# FRONT-UNIT-7.net
KiCad netlist of a schematic drawn in Altium Designer
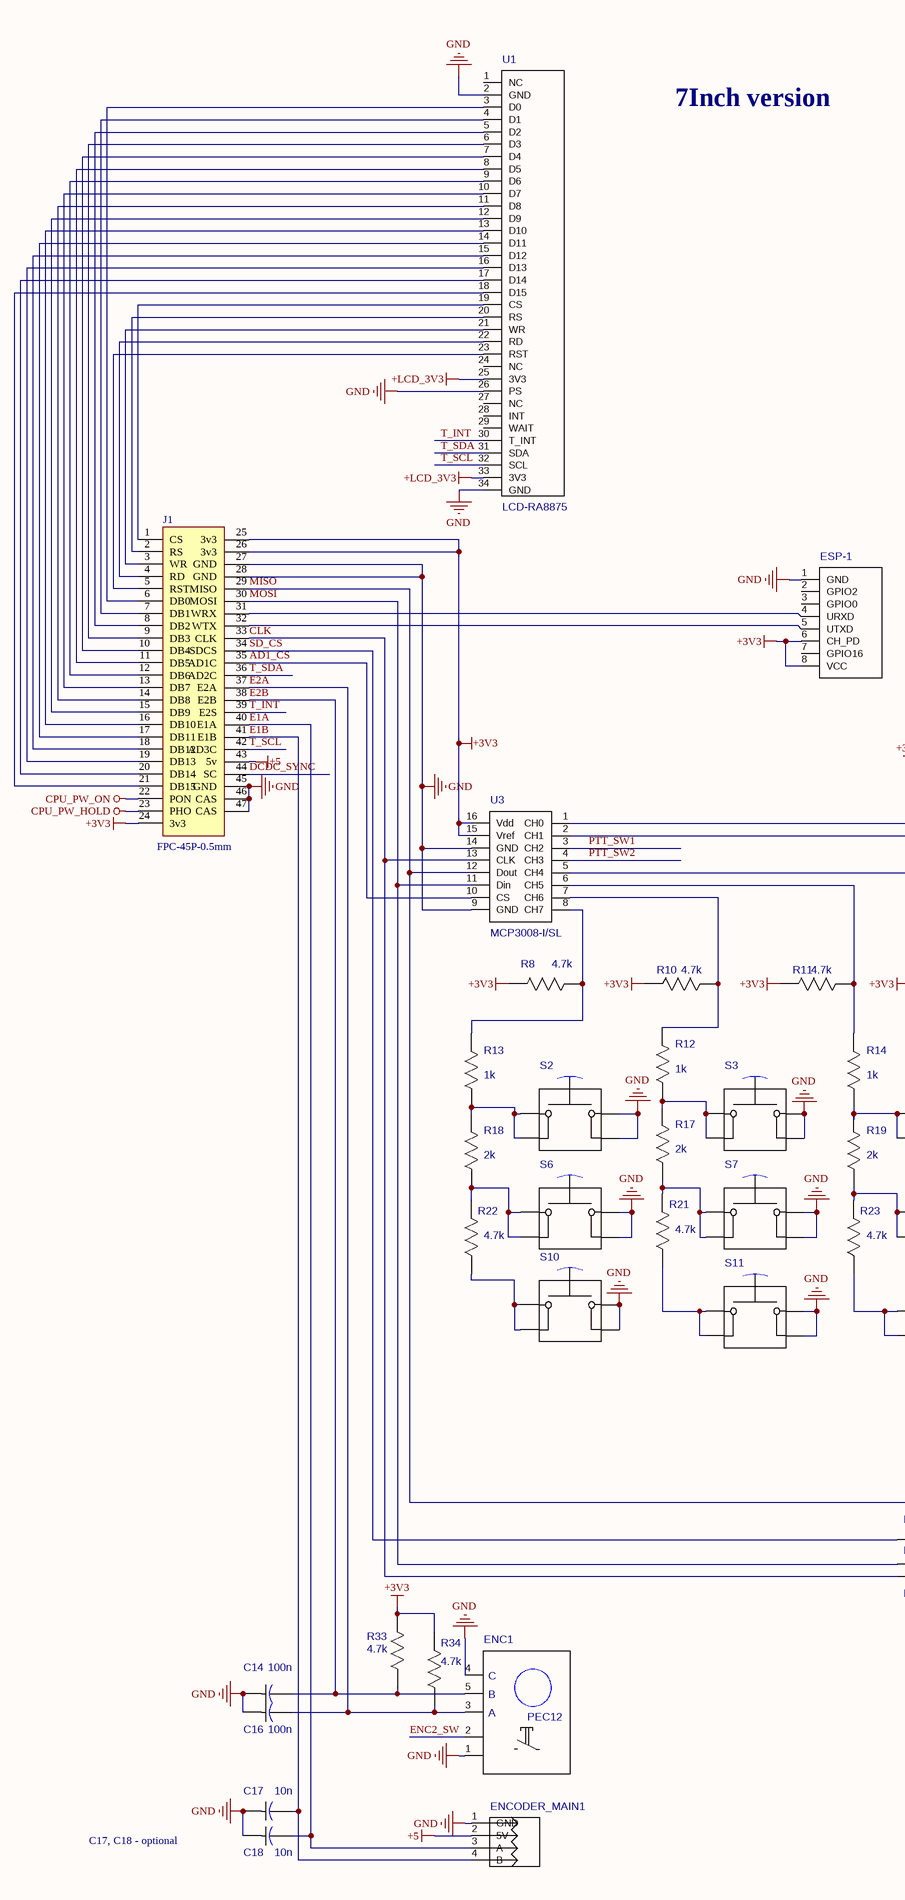
[diagram p0: FRONT-UNIT-7.SCHDOC, left]
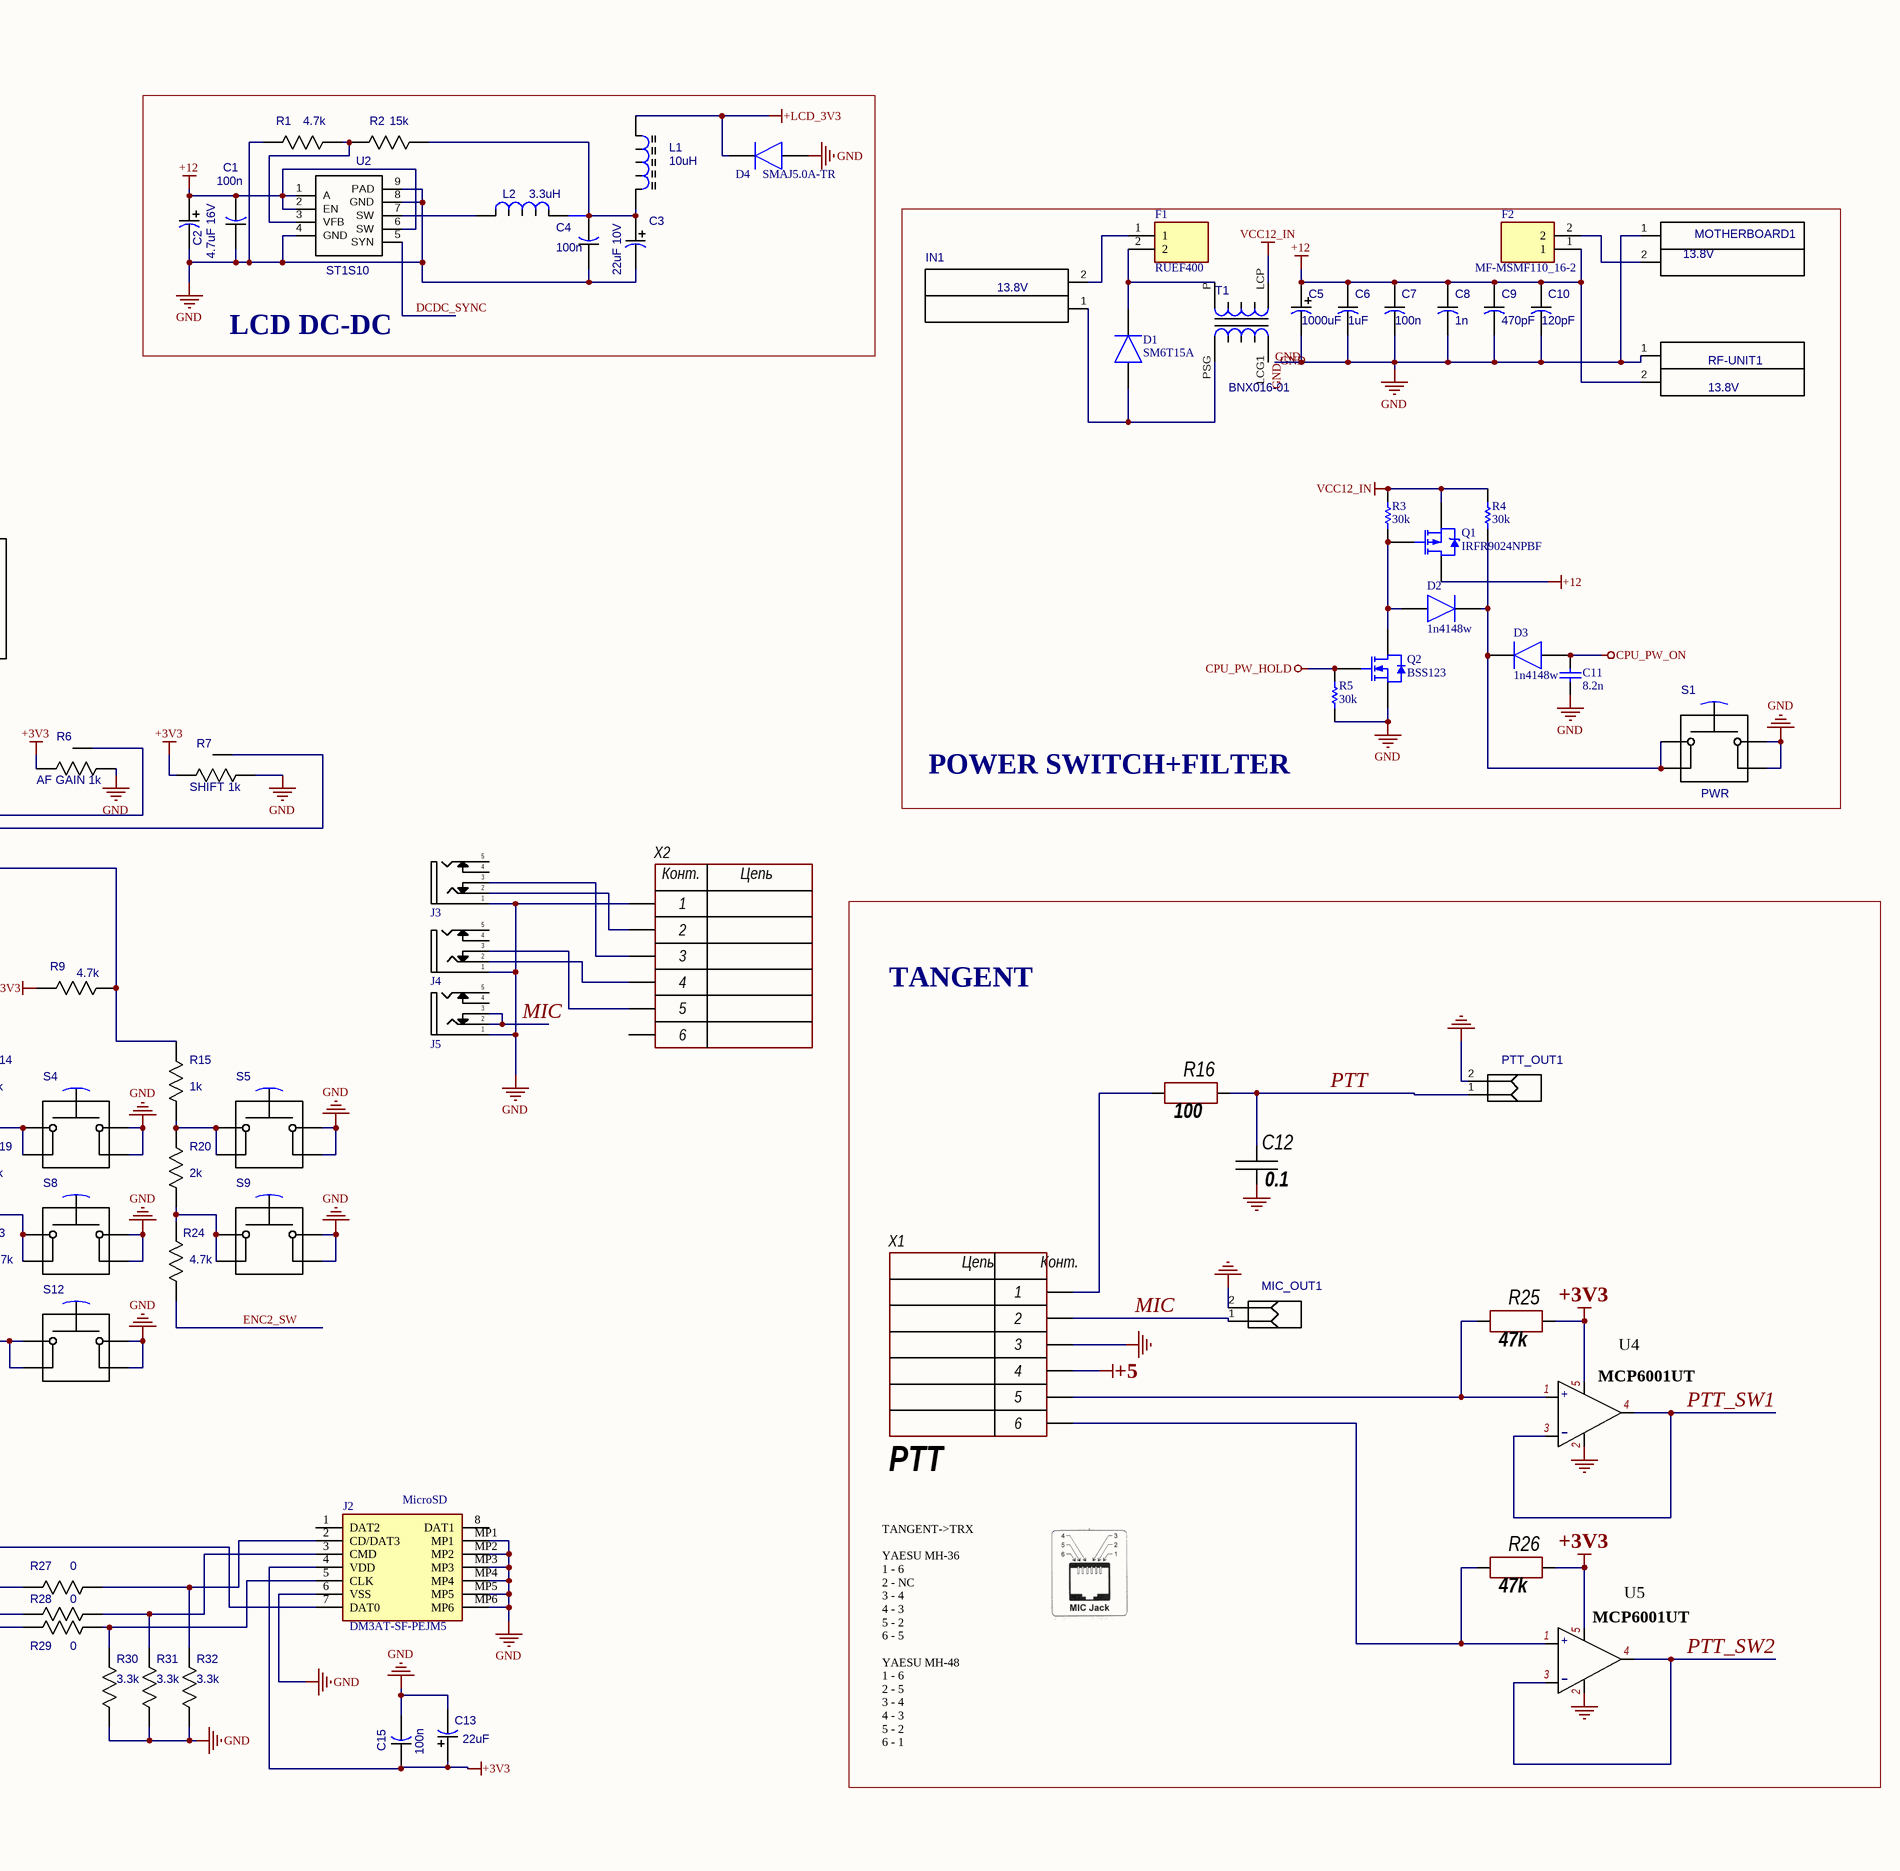
[diagram p1: FRONT-UNIT-7.SCHDOC, right]

(export (version "E")
  (design (tool "Eeschema 10.0.6"))
  (components
    (comp (ref "C1")
      (value "100n")
      (footprint "CAP_0805")
      (description "CAP_0805")
      (libsource (lib "*") (part "CAP_0805"))
    )
    (comp (ref "C2")
      (value "4.7uF 16V")
      (footprint "CAPAE_6.6x6.6h5.4")
      (description "CAPAE_6.6x6.6h5.4")
      (libsource (lib "*") (part "CAPAE_6.6x6.6h5.4"))
    )
    (comp (ref "C3")
      (value "22uF 10V")
      (footprint "CAPAE_4.3x4.3h5.4")
      (description "CAPAE_4.3x4.3h5.4")
      (libsource (lib "*") (part "CAPAE_4.3x4.3h5.4"))
    )
    (comp (ref "C4")
      (value "100n")
      (footprint "CAP_0805")
      (description "CAP_0805")
      (libsource (lib "FRONT-UNIT-7INCH") (part "CAP_0805"))
    )
    (comp (ref "C5")
      (value "1000uF")
      (footprint "CAP250RP")
      (description "CAP250RP")
      (libsource (lib "*") (part "CAP250RP"))
    )
    (comp (ref "C6")
      (value "1uF")
      (footprint "CAP_1206")
      (description "CAP_1206")
      (libsource (lib "*") (part "CAP_1206"))
    )
    (comp (ref "C7")
      (value "100n")
      (footprint "CAP_1206")
      (description "CAP_1206")
      (libsource (lib "*") (part "CAP_1206"))
    )
    (comp (ref "C8")
      (value "1n")
      (footprint "CAP_1206")
      (description "CAP_1206")
      (libsource (lib "*") (part "CAP_1206"))
    )
    (comp (ref "C9")
      (value "470pF")
      (footprint "CAP_1206")
      (description "CAP_1206")
      (libsource (lib "*") (part "CAP_1206"))
    )
    (comp (ref "C10")
      (value "120pF")
      (footprint "CAP_1206")
      (description "CAP_1206")
      (libsource (lib "FRONT-UNIT-7INCH") (part "CAP_1206"))
    )
    (comp (ref "C11")
      (value "8.2n")
      (footprint "CAPC2013X94X50LL20T25")
      (description "CAP_1206")
      (fields
        (field (name "MANUFACTURER") "AVX Interconnect / Elco")
        (field (name "PART NUMBER") "08055C822KAT2A")
      )
      (libsource (lib "Altium Content Vault") (part "CAP"))
    )
    (comp (ref "C12")
      (value "0.1")
      (footprint "CH0805C")
      (libsource (lib "FRONT-UNIT-7INCH") (part "Capacitor"))
    )
    (comp (ref "C13")
      (value "22uF")
      (footprint "EEEFC_sizeB")
      (description "EEEFC_sizeB")
      (libsource (lib "*") (part "EEEFC_sizeB"))
    )
    (comp (ref "C14")
      (value "100n")
      (footprint "CAP_0805")
      (description "CAP_0805")
      (libsource (lib "*") (part "CAP_0805"))
    )
    (comp (ref "C15")
      (value "100n")
      (footprint "CAP_0805")
      (description "CAP_0805")
      (libsource (lib "*") (part "CAP_0805"))
    )
    (comp (ref "C16")
      (value "100n")
      (footprint "CAP_0805")
      (description "CAP_0805")
      (libsource (lib "*") (part "CAP_0805"))
    )
    (comp (ref "C17")
      (value "10n")
      (footprint "CAP_0805")
      (description "CAP_0805")
      (libsource (lib "*") (part "CAP_0805"))
    )
    (comp (ref "C18")
      (value "10n")
      (footprint "CAP_0805")
      (description "CAP_0805")
      (libsource (lib "*") (part "CAP_0805"))
    )
    (comp (ref "D1")
      (value "SM6T15A")
      (footprint "SamacSys:SMBJ36CATR")
      (description "Diode")
      (fields (field (name "MOUSER PART NUMBER") "511-SM6T15A") (field (name "RS PART NUMBER") "4864915P"))
      (libsource (lib "*") (part "SM6T15A"))
    )
    (comp (ref "D2")
      (value "1n4148w")
      (footprint "SamacSys:SOD3716X135N")
      (description "Diode")
      (libsource (lib "*") (part "1n4148w"))
    )
    (comp (ref "D3")
      (value "1n4148w")
      (footprint "SamacSys:SOD3716X135N")
      (description "Diode")
      (libsource (lib "*") (part "1n4148w"))
    )
    (comp (ref "D4")
      (value "SMAJ5.0A-TR")
      (footprint "SamacSys:SMBJ36CATR")
      (description "Diode")
      (fields
        (field (name "MANUFACTURER_PART_NUMBER") "SMLVT3V3")
        (field (name "MOUSER PART NUMBER") "511-SMLVT3V3")
      )
      (libsource (lib "*") (part "SMLVT3V3"))
    )
    (comp (ref "ENC1") (value "PEC12") (footprint "PEC12") (libsource (lib "*") (part "PEC12")))
    (comp (ref "ENCODER_MAIN1")
      (value "OPTICAL ENCODER")
      (footprint "644456-4")
      (libsource (lib "*") (part "644456-4"))
    )
    (comp (ref "ESP-1")
      (value "ESP-01 ESP8266")
      (footprint "ESP-01 ESP8266")
      (libsource (lib "*") (part "ESP-01 ESP8266"))
    )
    (comp (ref "F1")
      (value "RUEF400")
      (footprint "SamacSys:RUEF400")
      (description "Fuse")
      (fields (field (name "MOUSER PART NUMBER") "650-RUEF400") (field (name "RS PART NUMBER") "5176837P"))
      (libsource (lib "*") (part "RUEF400"))
    )
    (comp (ref "F2")
      (value "MF-MSMF110_16-2")
      (footprint "SamacSys:FUSC4632X85N")
      (description "Fuse")
      (fields
        (field (name "MANUFACTURER_PART_NUMBER") "MF-MSMF110/16-2")
        (field (name "MOUSER PART NUMBER") "652-MF-MSMF110/16-2")
      )
      (libsource (lib "*") (part "MF-MSMF110_16-2"))
    )
    (comp (ref "IN1")
      (value "13.8V")
      (footprint "JX2")
      (description "JX2")
      (libsource (lib "*") (part "JX2"))
    )
    (comp (ref "J1")
      (value "FPC-45P-0.5mm")
      (footprint "FH12S45S05SH60")
      (description "Connector")
      (fields
        (field (name "MANUFACTURER_PART_NUMBER") "FH12S-45S-0.5SH(55)")
        (field (name "MOUSER PART NUMBER") "798-FH12S-45S-05SH55")
      )
      (libsource (lib "*") (part "FH12S-45S-0.5SH_55_"))
    )
    (comp (ref "J2")
      (value "DM3AT-SF-PEJM5")
      (footprint "SamacSys:DM3ATSFPEJM5")
      (description "Connector")
      (libsource (lib "*") (part "DM3AT-SF-PEJM5"))
    )
    (comp (ref "J3") (value "PJ-3,5") (footprint "Audio-PJ-392") (libsource (lib "SDR_ham") (part "PJ-3,5")))
    (comp (ref "J4") (value "PJ-3,5") (footprint "Audio-PJ-392") (libsource (lib "SDR_ham") (part "PJ-3,5")))
    (comp (ref "J5") (value "PJ-3,5") (footprint "Audio-PJ-392") (libsource (lib "SDR_ham") (part "PJ-3,5")))
    (comp (ref "L1")
      (value "10uH")
      (footprint "IND_FERRITE_CORE")
      (description "Inductor")
      (libsource (lib "FRONT-UNIT-7INCH") (part "IND_FERRITE_CORE"))
    )
    (comp (ref "L2")
      (value "3.3uH")
      (footprint "IND_1812")
      (description "IND_1812")
      (libsource (lib "*") (part "IND_1812"))
    )
    (comp (ref "MIC_OUT1")
      (value "MIC_OUT")
      (footprint "51022-0200")
      (description "51022-0200")
      (libsource (lib "*") (part "51022-0200"))
    )
    (comp (ref "MOTHERBOARD1")
      (value "13.8V")
      (footprint "JX2")
      (description "JX2")
      (libsource (lib "*") (part "JX2"))
    )
    (comp (ref "PTT_OUT1")
      (value "PTT_OUT")
      (footprint "51022-0200")
      (description "51022-0200")
      (libsource (lib "*") (part "51022-0200"))
    )
    (comp (ref "Q1")
      (value "IRFR9024NPBF")
      (footprint "ONSC-DPAK-3-369C-01_V")
      (description "IRFR9024NPBF, Транзистор, Р-канал 55В 11А")
      (fields (field (name "MANUFACTURER") "On Semiconductor") (field (name "PARTNUMBER") "NTD2955G"))
      (libsource (lib "Altium Content Vault") (part "ONSC-PMOS-G1S3D4-3_B"))
    )
    (comp (ref "Q2")
      (value "BSS123")
      (footprint "FAIR-SOT23-3_V")
      (fields (field (name "MANUFACTURER") "Fairchild"))
      (libsource (lib "Altium Content Vault") (part "NEMOS-GSD-3"))
    )
    (comp (ref "R1")
      (value "4.7k")
      (footprint "RES_0805")
      (description "RES_0805")
      (libsource (lib "") (part "RES_0805_1"))
    )
    (comp (ref "R2")
      (value "15k")
      (footprint "RES_0805")
      (description "RES_0805")
      (fields (field (name "Comment") "120k+100k"))
      (libsource (lib "") (part "RES_0805_1"))
    )
    (comp (ref "R3")
      (value "30k")
      (footprint "RESC2013X60X40NL20T25")
      (description "RES_0805")
      (fields (field (name "MANUFACTURER") "Panasonic") (field (name "PART NUMBER") "ERA-6AEB303V"))
      (libsource (lib "Altium Content Vault") (part "RES"))
    )
    (comp (ref "R4")
      (value "30k")
      (footprint "RESC2013X60X40NL20T25")
      (description "RES_0805")
      (fields (field (name "MANUFACTURER") "Panasonic") (field (name "PART NUMBER") "ERA-6AEB303V"))
      (libsource (lib "Altium Content Vault") (part "RES"))
    )
    (comp (ref "R5")
      (value "30k")
      (footprint "RESC2013X60X40NL20T25")
      (description "RES_0805")
      (fields (field (name "MANUFACTURER") "Panasonic") (field (name "PART NUMBER") "ERA-6AEB303V"))
      (libsource (lib "Altium Content Vault") (part "RES"))
    )
    (comp (ref "R6")
      (value "AF GAIN 1k")
      (footprint "PTV09")
      (description "Adjustable Resistor PTV09")
      (fields (field (name "Comment") "ptv09a-4225f-b102"))
      (libsource (lib "*") (part "PTV09"))
    )
    (comp (ref "R7")
      (value "SHIFT 1k")
      (footprint "PTV09")
      (description "Adjustable Resistor PTV09")
      (fields (field (name "Comment") "ptv09a-4225f-b102"))
      (libsource (lib "*") (part "PTV09"))
    )
    (comp (ref "R8")
      (value "4.7k")
      (footprint "RES_0805")
      (description "RES_0805")
      (libsource (lib "*") (part "RES_0805"))
    )
    (comp (ref "R9")
      (value "4.7k")
      (footprint "RES_0805")
      (description "RES_0805")
      (libsource (lib "*") (part "RES_0805"))
    )
    (comp (ref "R10")
      (value "4.7k")
      (footprint "RES_0805")
      (description "RES_0805")
      (libsource (lib "*") (part "RES_0805"))
    )
    (comp (ref "R11")
      (value "4.7k")
      (footprint "RES_0805")
      (description "RES_0805")
      (libsource (lib "*") (part "RES_0805"))
    )
    (comp (ref "R12")
      (value "1k")
      (footprint "RES_0805")
      (description "RES_0805")
      (libsource (lib "*") (part "RES_0805"))
    )
    (comp (ref "R13")
      (value "1k")
      (footprint "RES_0805")
      (description "RES_0805")
      (libsource (lib "*") (part "RES_0805"))
    )
    (comp (ref "R14")
      (value "1k")
      (footprint "RES_0805")
      (description "RES_0805")
      (libsource (lib "*") (part "RES_0805"))
    )
    (comp (ref "R15")
      (value "1k")
      (footprint "RES_0805")
      (description "RES_0805")
      (libsource (lib "*") (part "RES_0805"))
    )
    (comp (ref "R16")
      (value "100")
      (footprint "FRONT-UNIT-7INCH:CH0805R")
      (libsource (lib "Discrete") (part "Resistor"))
    )
    (comp (ref "R17")
      (value "2k")
      (footprint "RES_0805")
      (description "RES_0805")
      (libsource (lib "*") (part "RES_0805"))
    )
    (comp (ref "R18")
      (value "2k")
      (footprint "RES_0805")
      (description "RES_0805")
      (libsource (lib "*") (part "RES_0805"))
    )
    (comp (ref "R19")
      (value "2k")
      (footprint "RES_0805")
      (description "RES_0805")
      (libsource (lib "*") (part "RES_0805"))
    )
    (comp (ref "R20")
      (value "2k")
      (footprint "RES_0805")
      (description "RES_0805")
      (libsource (lib "*") (part "RES_0805"))
    )
    (comp (ref "R21")
      (value "4.7k")
      (footprint "RES_0805")
      (description "RES_0805")
      (libsource (lib "*") (part "RES_0805"))
    )
    (comp (ref "R22")
      (value "4.7k")
      (footprint "RES_0805")
      (description "RES_0805")
      (libsource (lib "*") (part "RES_0805"))
    )
    (comp (ref "R23")
      (value "4.7k")
      (footprint "RES_0805")
      (description "RES_0805")
      (libsource (lib "*") (part "RES_0805"))
    )
    (comp (ref "R24")
      (value "4.7k")
      (footprint "RES_0805")
      (description "RES_0805")
      (libsource (lib "*") (part "RES_0805"))
    )
    (comp (ref "R25")
      (value "47k")
      (footprint "FRONT-UNIT-7INCH:CH0805R")
      (libsource (lib "Discrete") (part "Resistor"))
    )
    (comp (ref "R26")
      (value "47k")
      (footprint "FRONT-UNIT-7INCH:CH0805C")
      (libsource (lib "Discrete") (part "Resistor"))
    )
    (comp (ref "R27")
      (value "0")
      (footprint "RES_0805")
      (description "RES_0805")
      (libsource (lib "*") (part "RES_0805"))
    )
    (comp (ref "R28")
      (value "0")
      (footprint "RES_0805")
      (description "RES_0805")
      (libsource (lib "*") (part "RES_0805"))
    )
    (comp (ref "R29")
      (value "0")
      (footprint "RES_0805")
      (description "RES_0805")
      (libsource (lib "*") (part "RES_0805"))
    )
    (comp (ref "R30")
      (value "3.3k")
      (footprint "RES_0805")
      (description "RES_0805")
      (libsource (lib "*") (part "RES_0805"))
    )
    (comp (ref "R31")
      (value "3.3k")
      (footprint "RES_0805")
      (description "RES_0805")
      (libsource (lib "*") (part "RES_0805"))
    )
    (comp (ref "R32")
      (value "3.3k")
      (footprint "RES_0805")
      (description "RES_0805")
      (libsource (lib "*") (part "RES_0805"))
    )
    (comp (ref "R33")
      (value "4.7k")
      (footprint "RES_0805")
      (description "RES_0805")
      (libsource (lib "*") (part "RES_0805"))
    )
    (comp (ref "R34")
      (value "4.7k")
      (footprint "RES_0805")
      (description "RES_0805")
      (libsource (lib "*") (part "RES_0805"))
    )
    (comp (ref "RF-UNIT1")
      (value "13.8V")
      (footprint "JX2")
      (description "JX2")
      (libsource (lib "*") (part "JX2"))
    )
    (comp (ref "S1")
      (value "PWR")
      (footprint "PTS645SK50LFS")
      (description "PTS645SK50LFS")
      (libsource (lib "*") (part "PTS645SK50LFS"))
    )
    (comp (ref "S2")
      (value "PTS645SK50LFS")
      (footprint "PTS645SK50LFS")
      (fields (field (name "LCSC PART #") "test"))
      (libsource (lib "*") (part "PTS645SK50LFS"))
    )
    (comp (ref "S3")
      (value "PTS645SK50LFS")
      (footprint "PTS645SK50LFS")
      (libsource (lib "*") (part "PTS645SK50LFS"))
    )
    (comp (ref "S4")
      (value "PTS645SK50LFS")
      (footprint "PTS645SK50LFS")
      (libsource (lib "*") (part "PTS645SK50LFS"))
    )
    (comp (ref "S5")
      (value "PTS645SK50LFS")
      (footprint "PTS645SK50LFS")
      (libsource (lib "*") (part "PTS645SK50LFS"))
    )
    (comp (ref "S6")
      (value "PTS645SK50LFS")
      (footprint "PTS645SK50LFS")
      (libsource (lib "*") (part "PTS645SK50LFS"))
    )
    (comp (ref "S7")
      (value "PTS645SK50LFS")
      (footprint "PTS645SK50LFS")
      (libsource (lib "*") (part "PTS645SK50LFS"))
    )
    (comp (ref "S8")
      (value "PTS645SK50LFS")
      (footprint "PTS645SK50LFS")
      (libsource (lib "*") (part "PTS645SK50LFS"))
    )
    (comp (ref "S9")
      (value "PTS645SK50LFS")
      (footprint "PTS645SK50LFS")
      (libsource (lib "*") (part "PTS645SK50LFS"))
    )
    (comp (ref "S10")
      (value "PTS645SK50LFS")
      (footprint "PTS645SK50LFS")
      (libsource (lib "*") (part "PTS645SK50LFS"))
    )
    (comp (ref "S11")
      (value "PTS645SK50LFS")
      (footprint "PTS645SK50LFS")
      (libsource (lib "*") (part "PTS645SK50LFS"))
    )
    (comp (ref "S12")
      (value "PTS645SK50LFS")
      (footprint "PTS645SK50LFS")
      (libsource (lib "*") (part "PTS645SK50LFS"))
    )
    (comp (ref "T1")
      (value "BNX016-01")
      (footprint "TRANSF_ICORE")
      (libsource (lib "*") (part "TRANSF_ICORE"))
    )
    (comp (ref "U1")
      (value "LCD-RA8875")
      (footprint "LCD-RA8875")
      (libsource (lib "FRONT-UNIT-7INCH") (part "LCD-RA8875"))
    )
    (comp (ref "U2") (value "ST1S10") (footprint "ST1S10") (libsource (lib "*") (part "ST1S10")))
    (comp (ref "U3")
      (value "MCP3008-I/SL")
      (footprint "MCP3008-I/SL")
      (libsource (lib "*") (part "MCP3008-I/SL"))
    )
    (comp (ref "U4")
      (value "MCP6001UT")
      (footprint "SOT23-5")
      (libsource (lib "Analog") (part "MCP6001UT_1"))
    )
    (comp (ref "U5")
      (value "MCP6001UT")
      (footprint "SOT23-5")
      (libsource (lib "Analog") (part "MCP6001UT_1"))
    )
    (comp (ref "X1")
      (value "PTT")
      (footprint "custom:CON: PLS-6")
      (libsource (lib "") (part "6-Connector_1"))
    )
    (comp (ref "X2")
      (value "PTT")
      (footprint "custom:CON: PLS-6")
      (libsource (lib "Connectors") (part "6-Connector"))
    )
  )
  (nets
    (net (code "1") (name "+3V3") (class "Default")
      (node (ref "C13") (pin "1") (pinfunction "PLUS_1") (pintype "passive"))
      (node (ref "C15") (pin "1") (pinfunction "1_1") (pintype "passive"))
      (node (ref "ESP-1") (pin "6") (pinfunction "CH_PD_6") (pintype "passive"))
      (node (ref "ESP-1") (pin "8") (pinfunction "VCC_8") (pintype "passive"))
      (node (ref "J1") (pin "24") (pinfunction "3v3_24") (pintype "passive"))
      (node (ref "J1") (pin "25") (pinfunction "3v3_25") (pintype "passive"))
      (node (ref "J1") (pin "26") (pinfunction "3v3_26") (pintype "passive"))
      (node (ref "J2") (pin "4") (pinfunction "VDD_4") (pintype "passive"))
      (node (ref "R10") (pin "2") (pinfunction "2_2") (pintype "passive"))
      (node (ref "R11") (pin "2") (pinfunction "2_2") (pintype "passive"))
      (node (ref "R25") (pin "2") (pinfunction "2_2") (pintype "passive"))
      (node (ref "R26") (pin "2") (pinfunction "2_2") (pintype "passive"))
      (node (ref "R33") (pin "2") (pinfunction "2_2") (pintype "passive"))
      (node (ref "R34") (pin "2") (pinfunction "2_2") (pintype "passive"))
      (node (ref "R6") (pin "1") (pinfunction "CW_1") (pintype "passive"))
      (node (ref "R7") (pin "1") (pinfunction "CW_1") (pintype "passive"))
      (node (ref "R8") (pin "2") (pinfunction "2_2") (pintype "passive"))
      (node (ref "R9") (pin "2") (pinfunction "2_2") (pintype "passive"))
      (node (ref "U3") (pin "15") (pinfunction "Vref_15") (pintype "passive"))
      (node (ref "U3") (pin "16") (pinfunction "Vdd_16") (pintype "passive"))
      (node (ref "U4") (pin "5") (pinfunction "5_5") (pintype "passive"))
      (node (ref "U5") (pin "5") (pinfunction "5_5") (pintype "passive"))
    )
    (net (code "2") (name "+5") (class "Default")
      (node (ref "ENCODER_MAIN1") (pin "2") (pinfunction "5V_2") (pintype "passive"))
      (node (ref "J1") (pin "43") (pinfunction "5v_43") (pintype "passive"))
      (node (ref "X1") (pin "4") (pinfunction "4_4") (pintype "power_in"))
    )
    (net (code "3") (name "+12") (class "Default")
      (node (ref "C1") (pin "2") (pinfunction "2_2") (pintype "passive"))
      (node (ref "C10") (pin "1") (pinfunction "1_1") (pintype "passive"))
      (node (ref "C2") (pin "1") (pinfunction "PLUS_1") (pintype "passive"))
      (node (ref "C5") (pin "1") (pinfunction "PLUS_1") (pintype "passive"))
      (node (ref "C6") (pin "1") (pinfunction "1_1") (pintype "passive"))
      (node (ref "C7") (pin "1") (pinfunction "1_1") (pintype "passive"))
      (node (ref "C8") (pin "1") (pinfunction "1_1") (pintype "passive"))
      (node (ref "C9") (pin "1") (pinfunction "1_1") (pintype "passive"))
      (node (ref "F2") (pin "1") (pinfunction "1_1") (pintype "passive"))
      (node (ref "Q1") (pin "4") (pinfunction "D_4") (pintype "passive"))
      (node (ref "RF-UNIT1") (pin "2") (pinfunction "1_2") (pintype "passive"))
      (node (ref "U2") (pin "1") (pinfunction "A_1") (pintype "passive"))
      (node (ref "U2") (pin "2") (pinfunction "EN_2") (pintype "passive"))
      (node (ref "U2") (pin "6") (pinfunction "SW_6") (pintype "passive"))
    )
    (net (code "4") (name "+LCD_3V3") (class "Default")
      (node (ref "D4") (pin "1") (pinfunction "K_1") (pintype "passive"))
      (node (ref "L1") (pin "1") (pinfunction "A_1") (pintype "passive"))
      (node (ref "U1") (pin "25") (pinfunction "3V3_25") (pintype "passive"))
      (node (ref "U1") (pin "33") (pinfunction "3V3_33") (pintype "passive"))
    )
    (net (code "5") (name "/AD1_CS") (class "Default")
      (node (ref "J1") (pin "35") (pinfunction "AD1C_35") (pintype "passive"))
      (node (ref "U3") (pin "10") (pinfunction "CS_10") (pintype "passive"))
    )
    (net (code "6") (name "/CLK") (class "Default")
      (node (ref "J1") (pin "33") (pinfunction "CLK_33") (pintype "passive"))
      (node (ref "R29") (pin "2") (pinfunction "2_2") (pintype "passive"))
      (node (ref "U3") (pin "13") (pinfunction "CLK_13") (pintype "passive"))
    )
    (net (code "7") (name "/DCDC_SYNC") (class "Default")
      (node (ref "J1") (pin "44") (pinfunction "SC_44") (pintype "passive"))
      (node (ref "U2") (pin "5") (pinfunction "SYN_5") (pintype "passive"))
    )
    (net (code "8") (name "/E1A") (class "Default")
      (node (ref "C18") (pin "2") (pinfunction "2_2") (pintype "passive"))
      (node (ref "ENCODER_MAIN1") (pin "3") (pinfunction "A_3") (pintype "passive"))
      (node (ref "J1") (pin "40") (pinfunction "E1A_40") (pintype "passive"))
    )
    (net (code "9") (name "/E1B") (class "Default")
      (node (ref "C17") (pin "2") (pinfunction "2_2") (pintype "passive"))
      (node (ref "ENCODER_MAIN1") (pin "4") (pinfunction "B_4") (pintype "passive"))
      (node (ref "J1") (pin "41") (pinfunction "E1B_41") (pintype "passive"))
    )
    (net (code "10") (name "/E2A") (class "Default")
      (node (ref "C16") (pin "2") (pinfunction "2_2") (pintype "passive"))
      (node (ref "ENC1") (pin "3") (pinfunction "A_3") (pintype "passive"))
      (node (ref "J1") (pin "37") (pinfunction "E2A_37") (pintype "passive"))
      (node (ref "R34") (pin "1") (pinfunction "1_1") (pintype "passive"))
    )
    (net (code "11") (name "/E2B") (class "Default")
      (node (ref "C14") (pin "2") (pinfunction "2_2") (pintype "passive"))
      (node (ref "ENC1") (pin "5") (pinfunction "B_5") (pintype "passive"))
      (node (ref "J1") (pin "38") (pinfunction "E2B_38") (pintype "passive"))
      (node (ref "R33") (pin "1") (pinfunction "1_1") (pintype "passive"))
    )
    (net (code "12") (name "/ENC2_SW") (class "Default")
      (node (ref "ENC1") (pin "2") (pinfunction "2_2") (pintype "passive"))
      (node (ref "R24") (pin "1") (pinfunction "1_1") (pintype "passive"))
    )
    (net (code "13") (name "/MIC") (class "Default")
      (node (ref "J5") (pin "2") (pinfunction "7_2") (pintype "passive"))
      (node (ref "J5") (pin "3") (pinfunction "6_3") (pintype "passive"))
      (node (ref "MIC_OUT1") (pin "1") (pinfunction "1_1") (pintype "passive"))
      (node (ref "X1") (pin "2") (pinfunction "2_2") (pintype "passive"))
    )
    (net (code "14") (name "/MISO") (class "Default")
      (node (ref "J1") (pin "29") (pinfunction "MISO_29") (pintype "passive"))
      (node (ref "J2") (pin "7") (pinfunction "DAT0_7") (pintype "passive"))
      (node (ref "U3") (pin "12") (pinfunction "Dout_12") (pintype "passive"))
    )
    (net (code "15") (name "/MOSI") (class "Default")
      (node (ref "J1") (pin "30") (pinfunction "MOSI_30") (pintype "passive"))
      (node (ref "R28") (pin "2") (pinfunction "2_2") (pintype "passive"))
      (node (ref "U3") (pin "11") (pinfunction "Din_11") (pintype "passive"))
    )
    (net (code "16") (name "/PTT") (class "Default")
      (node (ref "C12") (pin "2") (pinfunction "2_2") (pintype "power_in"))
      (node (ref "PTT_OUT1") (pin "1") (pinfunction "1_1") (pintype "passive"))
      (node (ref "R16") (pin "2") (pinfunction "2_2") (pintype "passive"))
    )
    (net (code "17") (name "/PTT_SW1") (class "Default")
      (node (ref "U3") (pin "3") (pinfunction "CH2_3") (pintype "passive"))
      (node (ref "U4") (pin "3") (pinfunction "3_3") (pintype "passive"))
      (node (ref "U4") (pin "4") (pinfunction "4_4") (pintype "passive"))
    )
    (net (code "18") (name "/PTT_SW2") (class "Default")
      (node (ref "U3") (pin "4") (pinfunction "CH3_4") (pintype "passive"))
      (node (ref "U5") (pin "3") (pinfunction "3_3") (pintype "passive"))
      (node (ref "U5") (pin "4") (pinfunction "4_4") (pintype "passive"))
    )
    (net (code "19") (name "/SD_CS") (class "Default")
      (node (ref "J1") (pin "34") (pinfunction "SDCS_34") (pintype "passive"))
      (node (ref "R27") (pin "2") (pinfunction "2_2") (pintype "passive"))
    )
    (net (code "20") (name "/T_INT") (class "Default")
      (node (ref "J1") (pin "39") (pinfunction "E2S_39") (pintype "passive"))
      (node (ref "U1") (pin "30") (pinfunction "T_INT_30") (pintype "passive"))
    )
    (net (code "21") (name "/T_SCL") (class "Default")
      (node (ref "J1") (pin "42") (pinfunction "AD3C_42") (pintype "passive"))
      (node (ref "U1") (pin "32") (pinfunction "SCL_32") (pintype "passive"))
    )
    (net (code "22") (name "/T_SDA") (class "Default")
      (node (ref "J1") (pin "36") (pinfunction "AD2C_36") (pintype "passive"))
      (node (ref "U1") (pin "31") (pinfunction "SDA_31") (pintype "passive"))
    )
    (net (code "23") (name "CPU_PW_HOLD") (class "Default")
      (node (ref "J1") (pin "23") (pinfunction "PHO_23") (pintype "passive"))
      (node (ref "Q2") (pin "1") (pinfunction "G_1") (pintype "passive"))
      (node (ref "R5") (pin "2") (pinfunction "2_2") (pintype "passive"))
    )
    (net (code "24") (name "CPU_PW_ON") (class "Default")
      (node (ref "C11") (pin "2") (pinfunction "2_2") (pintype "passive"))
      (node (ref "D3") (pin "2") (pinfunction "A_2") (pintype "passive"))
      (node (ref "J1") (pin "22") (pinfunction "PON_22") (pintype "passive"))
    )
    (net (code "25") (name "GND") (class "Default")
      (node (ref "C1") (pin "1") (pinfunction "1_1") (pintype "passive"))
      (node (ref "C10") (pin "2") (pinfunction "2_2") (pintype "passive"))
      (node (ref "C11") (pin "1") (pinfunction "1_1") (pintype "passive"))
      (node (ref "C12") (pin "1") (pinfunction "1_1") (pintype "power_in"))
      (node (ref "C13") (pin "2") (pinfunction "MINUS_2") (pintype "passive"))
      (node (ref "C14") (pin "1") (pinfunction "1_1") (pintype "passive"))
      (node (ref "C15") (pin "2") (pinfunction "2_2") (pintype "passive"))
      (node (ref "C16") (pin "1") (pinfunction "1_1") (pintype "passive"))
      (node (ref "C17") (pin "1") (pinfunction "1_1") (pintype "passive"))
      (node (ref "C18") (pin "1") (pinfunction "1_1") (pintype "passive"))
      (node (ref "C2") (pin "2") (pinfunction "MINUS_2") (pintype "passive"))
      (node (ref "C3") (pin "2") (pinfunction "MINUS_2") (pintype "passive"))
      (node (ref "C4") (pin "1") (pinfunction "1_1") (pintype "passive"))
      (node (ref "C5") (pin "2") (pinfunction "MINUS_2") (pintype "passive"))
      (node (ref "C6") (pin "2") (pinfunction "2_2") (pintype "passive"))
      (node (ref "C7") (pin "2") (pinfunction "2_2") (pintype "passive"))
      (node (ref "C8") (pin "2") (pinfunction "2_2") (pintype "passive"))
      (node (ref "C9") (pin "2") (pinfunction "2_2") (pintype "passive"))
      (node (ref "D4") (pin "2") (pinfunction "A_2") (pintype "passive"))
      (node (ref "ENC1") (pin "1") (pinfunction "1_1") (pintype "passive"))
      (node (ref "ENC1") (pin "4") (pinfunction "C_4") (pintype "passive"))
      (node (ref "ENCODER_MAIN1") (pin "1") (pinfunction "GND_1") (pintype "passive"))
      (node (ref "ESP-1") (pin "1") (pinfunction "GND_1") (pintype "passive"))
      (node (ref "J1") (pin "27") (pinfunction "GND_27") (pintype "passive"))
      (node (ref "J1") (pin "28") (pinfunction "GND_28") (pintype "passive"))
      (node (ref "J1") (pin "45") (pinfunction "GND_45") (pintype "passive"))
      (node (ref "J1") (pin "46") (pinfunction "CAS_46") (pintype "passive"))
      (node (ref "J1") (pin "47") (pinfunction "CAS_47") (pintype "passive"))
      (node (ref "J2") (pin "6") (pinfunction "VSS_6") (pintype "passive"))
      (node (ref "J2") (pin "MP1") (pinfunction "MP1_MP1") (pintype "passive"))
      (node (ref "J2") (pin "MP2") (pinfunction "MP2_MP2") (pintype "passive"))
      (node (ref "J2") (pin "MP3") (pinfunction "MP3_MP3") (pintype "passive"))
      (node (ref "J2") (pin "MP4") (pinfunction "MP4_MP4") (pintype "passive"))
      (node (ref "J2") (pin "MP5") (pinfunction "MP5_MP5") (pintype "passive"))
      (node (ref "J2") (pin "MP6") (pinfunction "MP6_MP6") (pintype "passive"))
      (node (ref "J3") (pin "1") (pinfunction "8_1") (pintype "passive"))
      (node (ref "J4") (pin "1") (pinfunction "8_1") (pintype "passive"))
      (node (ref "J5") (pin "1") (pinfunction "8_1") (pintype "passive"))
      (node (ref "MIC_OUT1") (pin "2") (pinfunction "2_2") (pintype "passive"))
      (node (ref "MOTHERBOARD1") (pin "1") (pinfunction "2_1") (pintype "passive"))
      (node (ref "PTT_OUT1") (pin "2") (pinfunction "2_2") (pintype "passive"))
      (node (ref "Q2") (pin "2") (pinfunction "S_2") (pintype "passive"))
      (node (ref "R1") (pin "1") (pinfunction "1_1") (pintype "passive"))
      (node (ref "R30") (pin "1") (pinfunction "1_1") (pintype "passive"))
      (node (ref "R31") (pin "1") (pinfunction "1_1") (pintype "passive"))
      (node (ref "R32") (pin "1") (pinfunction "1_1") (pintype "passive"))
      (node (ref "R5") (pin "1") (pinfunction "1_1") (pintype "passive"))
      (node (ref "R6") (pin "3") (pinfunction "CCW_3") (pintype "passive"))
      (node (ref "R7") (pin "3") (pinfunction "CCW_3") (pintype "passive"))
      (node (ref "RF-UNIT1") (pin "1") (pinfunction "2_1") (pintype "passive"))
      (node (ref "S1") (pin "3") (pinfunction "B_3") (pintype "passive"))
      (node (ref "S1") (pin "4") (pinfunction "B_4") (pintype "passive"))
      (node (ref "S10") (pin "3") (pinfunction "B_3") (pintype "passive"))
      (node (ref "S10") (pin "4") (pinfunction "B_4") (pintype "passive"))
      (node (ref "S11") (pin "3") (pinfunction "B_3") (pintype "passive"))
      (node (ref "S11") (pin "4") (pinfunction "B_4") (pintype "passive"))
      (node (ref "S12") (pin "3") (pinfunction "B_3") (pintype "passive"))
      (node (ref "S12") (pin "4") (pinfunction "B_4") (pintype "passive"))
      (node (ref "S2") (pin "3") (pinfunction "B_3") (pintype "passive"))
      (node (ref "S2") (pin "4") (pinfunction "B_4") (pintype "passive"))
      (node (ref "S3") (pin "3") (pinfunction "B_3") (pintype "passive"))
      (node (ref "S3") (pin "4") (pinfunction "B_4") (pintype "passive"))
      (node (ref "S4") (pin "3") (pinfunction "B_3") (pintype "passive"))
      (node (ref "S4") (pin "4") (pinfunction "B_4") (pintype "passive"))
      (node (ref "S5") (pin "3") (pinfunction "B_3") (pintype "passive"))
      (node (ref "S5") (pin "4") (pinfunction "B_4") (pintype "passive"))
      (node (ref "S6") (pin "3") (pinfunction "B_3") (pintype "passive"))
      (node (ref "S6") (pin "4") (pinfunction "B_4") (pintype "passive"))
      (node (ref "S7") (pin "3") (pinfunction "B_3") (pintype "passive"))
      (node (ref "S7") (pin "4") (pinfunction "B_4") (pintype "passive"))
      (node (ref "S8") (pin "3") (pinfunction "B_3") (pintype "passive"))
      (node (ref "S8") (pin "4") (pinfunction "B_4") (pintype "passive"))
      (node (ref "S9") (pin "3") (pinfunction "B_3") (pintype "passive"))
      (node (ref "S9") (pin "4") (pinfunction "B_4") (pintype "passive"))
      (node (ref "T1") (pin "LCG1") (pinfunction "S2_LCG1") (pintype "passive"))
      (node (ref "U1") (pin "2") (pinfunction "GND_2") (pintype "passive"))
      (node (ref "U1") (pin "26") (pinfunction "PS_26") (pintype "passive"))
      (node (ref "U1") (pin "34") (pinfunction "GND_34") (pintype "passive"))
      (node (ref "U2") (pin "4") (pinfunction "GND_4") (pintype "passive"))
      (node (ref "U2") (pin "8") (pinfunction "GND_8") (pintype "passive"))
      (node (ref "U2") (pin "9") (pinfunction "PAD_9") (pintype "passive"))
      (node (ref "U3") (pin "14") (pinfunction "GND_14") (pintype "passive"))
      (node (ref "U3") (pin "9") (pinfunction "GND_9") (pintype "passive"))
      (node (ref "U4") (pin "2") (pinfunction "2_2") (pintype "passive"))
      (node (ref "U5") (pin "2") (pinfunction "2_2") (pintype "passive"))
      (node (ref "X1") (pin "3") (pinfunction "3_3") (pintype "power_in"))
      (node (ref "X2") (pin "1") (pinfunction "1_1") (pintype "passive"))
    )
    (net (code "26") (name "Net-(C3-PLUS)") (class "Default")
      (node (ref "C3") (pin "1") (pinfunction "PLUS_1") (pintype "passive"))
      (node (ref "C4") (pin "2") (pinfunction "2_2") (pintype "passive"))
      (node (ref "L1") (pin "2") (pinfunction "B_2") (pintype "passive"))
      (node (ref "L2") (pin "2") (pinfunction "2_2") (pintype "passive"))
      (node (ref "R2") (pin "2") (pinfunction "2_2") (pintype "passive"))
    )
    (net (code "27") (name "Net-(D1-A)") (class "Default")
      (node (ref "D1") (pin "2") (pinfunction "A_2") (pintype "passive"))
      (node (ref "IN1") (pin "1") (pinfunction "2_1") (pintype "passive"))
      (node (ref "T1") (pin "PSG") (pinfunction "S1_PSG") (pintype "passive"))
    )
    (net (code "28") (name "Net-(D1-K)") (class "Default")
      (node (ref "D1") (pin "1") (pinfunction "K_1") (pintype "passive"))
      (node (ref "F1") (pin "2") (pinfunction "2_2") (pintype "passive"))
      (node (ref "T1") (pin "P") (pinfunction "P1_P") (pintype "passive"))
    )
    (net (code "29") (name "Net-(D2-A)") (class "Default")
      (node (ref "D2") (pin "2") (pinfunction "A_2") (pintype "passive"))
      (node (ref "Q1") (pin "1") (pinfunction "G_1") (pintype "passive"))
      (node (ref "Q2") (pin "3") (pinfunction "D_3") (pintype "passive"))
      (node (ref "R3") (pin "1") (pinfunction "1_1") (pintype "passive"))
    )
    (net (code "30") (name "Net-(D2-K)") (class "Default")
      (node (ref "D2") (pin "1") (pinfunction "K_1") (pintype "passive"))
      (node (ref "D3") (pin "1") (pinfunction "K_1") (pintype "passive"))
      (node (ref "R4") (pin "1") (pinfunction "1_1") (pintype "passive"))
      (node (ref "S1") (pin "1") (pinfunction "A_1") (pintype "passive"))
      (node (ref "S1") (pin "2") (pinfunction "A_2") (pintype "passive"))
    )
    (net (code "31") (name "Net-(ESP-1-URXD)") (class "Default")
      (node (ref "ESP-1") (pin "4") (pinfunction "URXD_4") (pintype "passive"))
      (node (ref "J1") (pin "31") (pinfunction "WRX_31") (pintype "passive"))
    )
    (net (code "32") (name "Net-(ESP-1-UTXD)") (class "Default")
      (node (ref "ESP-1") (pin "5") (pinfunction "UTXD_5") (pintype "passive"))
      (node (ref "J1") (pin "32") (pinfunction "WTX_32") (pintype "passive"))
    )
    (net (code "33") (name "Net-(IN1-1)") (class "Default")
      (node (ref "F1") (pin "1") (pinfunction "1_1") (pintype "passive"))
      (node (ref "IN1") (pin "2") (pinfunction "1_2") (pintype "passive"))
    )
    (net (code "34") (name "Net-(J1-CS)") (class "Default")
      (node (ref "J1") (pin "1") (pinfunction "CS_1") (pintype "passive"))
      (node (ref "U1") (pin "19") (pinfunction "CS_19") (pintype "passive"))
    )
    (net (code "35") (name "Net-(J1-DB0)") (class "Default")
      (node (ref "J1") (pin "6") (pinfunction "DB0_6") (pintype "passive"))
      (node (ref "U1") (pin "3") (pinfunction "D0_3") (pintype "passive"))
    )
    (net (code "36") (name "Net-(J1-DB1)") (class "Default")
      (node (ref "J1") (pin "7") (pinfunction "DB1_7") (pintype "passive"))
      (node (ref "U1") (pin "4") (pinfunction "D1_4") (pintype "passive"))
    )
    (net (code "37") (name "Net-(J1-DB2)") (class "Default")
      (node (ref "J1") (pin "8") (pinfunction "DB2_8") (pintype "passive"))
      (node (ref "U1") (pin "5") (pinfunction "D2_5") (pintype "passive"))
    )
    (net (code "38") (name "Net-(J1-DB3)") (class "Default")
      (node (ref "J1") (pin "9") (pinfunction "DB3_9") (pintype "passive"))
      (node (ref "U1") (pin "6") (pinfunction "D3_6") (pintype "passive"))
    )
    (net (code "39") (name "Net-(J1-DB4)") (class "Default")
      (node (ref "J1") (pin "10") (pinfunction "DB4_10") (pintype "passive"))
      (node (ref "U1") (pin "7") (pinfunction "D4_7") (pintype "passive"))
    )
    (net (code "40") (name "Net-(J1-DB5)") (class "Default")
      (node (ref "J1") (pin "11") (pinfunction "DB5_11") (pintype "passive"))
      (node (ref "U1") (pin "8") (pinfunction "D5_8") (pintype "passive"))
    )
    (net (code "41") (name "Net-(J1-DB6)") (class "Default")
      (node (ref "J1") (pin "12") (pinfunction "DB6_12") (pintype "passive"))
      (node (ref "U1") (pin "9") (pinfunction "D6_9") (pintype "passive"))
    )
    (net (code "42") (name "Net-(J1-DB7)") (class "Default")
      (node (ref "J1") (pin "13") (pinfunction "DB7_13") (pintype "passive"))
      (node (ref "U1") (pin "10") (pinfunction "D7_10") (pintype "passive"))
    )
    (net (code "43") (name "Net-(J1-DB8)") (class "Default")
      (node (ref "J1") (pin "14") (pinfunction "DB8_14") (pintype "passive"))
      (node (ref "U1") (pin "11") (pinfunction "D8_11") (pintype "passive"))
    )
    (net (code "44") (name "Net-(J1-DB9)") (class "Default")
      (node (ref "J1") (pin "15") (pinfunction "DB9_15") (pintype "passive"))
      (node (ref "U1") (pin "12") (pinfunction "D9_12") (pintype "passive"))
    )
    (net (code "45") (name "Net-(J1-DB10)") (class "Default")
      (node (ref "J1") (pin "16") (pinfunction "DB10_16") (pintype "passive"))
      (node (ref "U1") (pin "13") (pinfunction "D10_13") (pintype "passive"))
    )
    (net (code "46") (name "Net-(J1-DB11)") (class "Default")
      (node (ref "J1") (pin "17") (pinfunction "DB11_17") (pintype "passive"))
      (node (ref "U1") (pin "14") (pinfunction "D11_14") (pintype "passive"))
    )
    (net (code "47") (name "Net-(J1-DB12)") (class "Default")
      (node (ref "J1") (pin "18") (pinfunction "DB12_18") (pintype "passive"))
      (node (ref "U1") (pin "15") (pinfunction "D12_15") (pintype "passive"))
    )
    (net (code "48") (name "Net-(J1-DB13)") (class "Default")
      (node (ref "J1") (pin "19") (pinfunction "DB13_19") (pintype "passive"))
      (node (ref "U1") (pin "16") (pinfunction "D13_16") (pintype "passive"))
    )
    (net (code "49") (name "Net-(J1-DB14)") (class "Default")
      (node (ref "J1") (pin "20") (pinfunction "DB14_20") (pintype "passive"))
      (node (ref "U1") (pin "17") (pinfunction "D14_17") (pintype "passive"))
    )
    (net (code "50") (name "Net-(J1-DB15)") (class "Default")
      (node (ref "J1") (pin "21") (pinfunction "DB15_21") (pintype "passive"))
      (node (ref "U1") (pin "18") (pinfunction "D15_18") (pintype "passive"))
    )
    (net (code "51") (name "Net-(J1-RD)") (class "Default")
      (node (ref "J1") (pin "4") (pinfunction "RD_4") (pintype "passive"))
      (node (ref "U1") (pin "22") (pinfunction "RD_22") (pintype "passive"))
    )
    (net (code "52") (name "Net-(J1-RS)") (class "Default")
      (node (ref "J1") (pin "2") (pinfunction "RS_2") (pintype "passive"))
      (node (ref "U1") (pin "20") (pinfunction "RS_20") (pintype "passive"))
    )
    (net (code "53") (name "Net-(J1-RST)") (class "Default")
      (node (ref "J1") (pin "5") (pinfunction "RST_5") (pintype "passive"))
      (node (ref "U1") (pin "23") (pinfunction "RST_23") (pintype "passive"))
    )
    (net (code "54") (name "Net-(J1-WR)") (class "Default")
      (node (ref "J1") (pin "3") (pinfunction "WR_3") (pintype "passive"))
      (node (ref "U1") (pin "21") (pinfunction "WR_21") (pintype "passive"))
    )
    (net (code "55") (name "Net-(J2-CD{slash}DAT3)") (class "Default")
      (node (ref "J2") (pin "2") (pinfunction "CD/DAT3_2") (pintype "passive"))
      (node (ref "R27") (pin "1") (pinfunction "1_1") (pintype "passive"))
      (node (ref "R32") (pin "2") (pinfunction "2_2") (pintype "passive"))
    )
    (net (code "56") (name "Net-(J2-CLK)") (class "Default")
      (node (ref "J2") (pin "5") (pinfunction "CLK_5") (pintype "passive"))
      (node (ref "R29") (pin "1") (pinfunction "1_1") (pintype "passive"))
      (node (ref "R30") (pin "2") (pinfunction "2_2") (pintype "passive"))
    )
    (net (code "57") (name "Net-(J2-CMD)") (class "Default")
      (node (ref "J2") (pin "3") (pinfunction "CMD_3") (pintype "passive"))
      (node (ref "R28") (pin "1") (pinfunction "1_1") (pintype "passive"))
      (node (ref "R31") (pin "2") (pinfunction "2_2") (pintype "passive"))
    )
    (net (code "58") (name "Net-(J3-6)") (class "Default")
      (node (ref "J3") (pin "3") (pinfunction "6_3") (pintype "passive"))
      (node (ref "X2") (pin "3") (pinfunction "3_3") (pintype "power_in"))
    )
    (net (code "59") (name "Net-(J3-7)") (class "Default")
      (node (ref "J3") (pin "2") (pinfunction "7_2") (pintype "passive"))
      (node (ref "X2") (pin "2") (pinfunction "2_2") (pintype "passive"))
    )
    (net (code "60") (name "Net-(J4-6)") (class "Default")
      (node (ref "J4") (pin "3") (pinfunction "6_3") (pintype "passive"))
      (node (ref "X2") (pin "5") (pinfunction "5_5") (pintype "power_in"))
    )
    (net (code "61") (name "Net-(J4-7)") (class "Default")
      (node (ref "J4") (pin "2") (pinfunction "7_2") (pintype "passive"))
      (node (ref "X2") (pin "4") (pinfunction "4_4") (pintype "power_in"))
    )
    (net (code "62") (name "Net-(L2-Pad1)") (class "Default")
      (node (ref "L2") (pin "1") (pinfunction "1_1") (pintype "passive"))
      (node (ref "U2") (pin "7") (pinfunction "SW_7") (pintype "passive"))
    )
    (net (code "63") (name "Net-(MOTHERBOARD1-1)") (class "Default")
      (node (ref "F2") (pin "2") (pinfunction "2_2") (pintype "passive"))
      (node (ref "MOTHERBOARD1") (pin "2") (pinfunction "1_2") (pintype "passive"))
    )
    (net (code "64") (name "Net-(R6-W)") (class "Default")
      (node (ref "R6") (pin "2") (pinfunction "W_2") (pintype "passive"))
      (node (ref "U3") (pin "1") (pinfunction "CH0_1") (pintype "passive"))
    )
    (net (code "65") (name "Net-(R7-W)") (class "Default")
      (node (ref "R7") (pin "2") (pinfunction "W_2") (pintype "passive"))
      (node (ref "U3") (pin "2") (pinfunction "CH1_2") (pintype "passive"))
    )
    (net (code "66") (name "Net-(R12-Pad1)") (class "Default")
      (node (ref "R12") (pin "1") (pinfunction "1_1") (pintype "passive"))
      (node (ref "R17") (pin "2") (pinfunction "2_2") (pintype "passive"))
      (node (ref "S3") (pin "1") (pinfunction "A_1") (pintype "passive"))
      (node (ref "S3") (pin "2") (pinfunction "A_2") (pintype "passive"))
    )
    (net (code "67") (name "Net-(R13-Pad1)") (class "Default")
      (node (ref "R13") (pin "1") (pinfunction "1_1") (pintype "passive"))
      (node (ref "R18") (pin "2") (pinfunction "2_2") (pintype "passive"))
      (node (ref "S2") (pin "1") (pinfunction "A_1") (pintype "passive"))
      (node (ref "S2") (pin "2") (pinfunction "A_2") (pintype "passive"))
    )
    (net (code "68") (name "Net-(R14-Pad1)") (class "Default")
      (node (ref "R14") (pin "1") (pinfunction "1_1") (pintype "passive"))
      (node (ref "R19") (pin "2") (pinfunction "2_2") (pintype "passive"))
      (node (ref "S4") (pin "1") (pinfunction "A_1") (pintype "passive"))
      (node (ref "S4") (pin "2") (pinfunction "A_2") (pintype "passive"))
    )
    (net (code "69") (name "Net-(R15-Pad1)") (class "Default")
      (node (ref "R15") (pin "1") (pinfunction "1_1") (pintype "passive"))
      (node (ref "R20") (pin "2") (pinfunction "2_2") (pintype "passive"))
      (node (ref "S5") (pin "1") (pinfunction "A_1") (pintype "passive"))
      (node (ref "S5") (pin "2") (pinfunction "A_2") (pintype "passive"))
    )
    (net (code "70") (name "Net-(R16-Pad1)") (class "Default")
      (node (ref "R16") (pin "1") (pinfunction "1_1") (pintype "passive"))
      (node (ref "X1") (pin "1") (pinfunction "1_1") (pintype "passive"))
    )
    (net (code "71") (name "Net-(R17-Pad1)") (class "Default")
      (node (ref "R17") (pin "1") (pinfunction "1_1") (pintype "passive"))
      (node (ref "R21") (pin "2") (pinfunction "2_2") (pintype "passive"))
      (node (ref "S7") (pin "1") (pinfunction "A_1") (pintype "passive"))
      (node (ref "S7") (pin "2") (pinfunction "A_2") (pintype "passive"))
    )
    (net (code "72") (name "Net-(R18-Pad1)") (class "Default")
      (node (ref "R18") (pin "1") (pinfunction "1_1") (pintype "passive"))
      (node (ref "R22") (pin "2") (pinfunction "2_2") (pintype "passive"))
      (node (ref "S6") (pin "1") (pinfunction "A_1") (pintype "passive"))
      (node (ref "S6") (pin "2") (pinfunction "A_2") (pintype "passive"))
    )
    (net (code "73") (name "Net-(R19-Pad1)") (class "Default")
      (node (ref "R19") (pin "1") (pinfunction "1_1") (pintype "passive"))
      (node (ref "R23") (pin "2") (pinfunction "2_2") (pintype "passive"))
      (node (ref "S8") (pin "1") (pinfunction "A_1") (pintype "passive"))
      (node (ref "S8") (pin "2") (pinfunction "A_2") (pintype "passive"))
    )
    (net (code "74") (name "Net-(R20-Pad1)") (class "Default")
      (node (ref "R20") (pin "1") (pinfunction "1_1") (pintype "passive"))
      (node (ref "R24") (pin "2") (pinfunction "2_2") (pintype "passive"))
      (node (ref "S9") (pin "1") (pinfunction "A_1") (pintype "passive"))
      (node (ref "S9") (pin "2") (pinfunction "A_2") (pintype "passive"))
    )
    (net (code "75") (name "Net-(R21-Pad1)") (class "Default")
      (node (ref "R21") (pin "1") (pinfunction "1_1") (pintype "passive"))
      (node (ref "S11") (pin "1") (pinfunction "A_1") (pintype "passive"))
      (node (ref "S11") (pin "2") (pinfunction "A_2") (pintype "passive"))
    )
    (net (code "76") (name "Net-(R22-Pad1)") (class "Default")
      (node (ref "R22") (pin "1") (pinfunction "1_1") (pintype "passive"))
      (node (ref "S10") (pin "1") (pinfunction "A_1") (pintype "passive"))
      (node (ref "S10") (pin "2") (pinfunction "A_2") (pintype "passive"))
    )
    (net (code "77") (name "Net-(R23-Pad1)") (class "Default")
      (node (ref "R23") (pin "1") (pinfunction "1_1") (pintype "passive"))
      (node (ref "S12") (pin "1") (pinfunction "A_1") (pintype "passive"))
      (node (ref "S12") (pin "2") (pinfunction "A_2") (pintype "passive"))
    )
    (net (code "78") (name "Net-(R25-Pad1)") (class "Default")
      (node (ref "R25") (pin "1") (pinfunction "1_1") (pintype "passive"))
      (node (ref "U4") (pin "1") (pinfunction "1_1") (pintype "passive"))
      (node (ref "X1") (pin "5") (pinfunction "5_5") (pintype "power_in"))
    )
    (net (code "79") (name "Net-(R26-Pad1)") (class "Default")
      (node (ref "R26") (pin "1") (pinfunction "1_1") (pintype "passive"))
      (node (ref "U5") (pin "1") (pinfunction "1_1") (pintype "passive"))
      (node (ref "X1") (pin "6") (pinfunction "6_6") (pintype "power_in"))
    )
    (net (code "80") (name "Net-(U2-VFB)") (class "Default")
      (node (ref "R1") (pin "2") (pinfunction "2_2") (pintype "passive"))
      (node (ref "R2") (pin "1") (pinfunction "1_1") (pintype "passive"))
      (node (ref "U2") (pin "3") (pinfunction "VFB_3") (pintype "passive"))
    )
    (net (code "81") (name "Net-(U3-CH4)") (class "Default")
      (node (ref "R15") (pin "2") (pinfunction "2_2") (pintype "passive"))
      (node (ref "R9") (pin "1") (pinfunction "1_1") (pintype "passive"))
      (node (ref "U3") (pin "5") (pinfunction "CH4_5") (pintype "passive"))
    )
    (net (code "82") (name "Net-(U3-CH5)") (class "Default")
      (node (ref "R11") (pin "1") (pinfunction "1_1") (pintype "passive"))
      (node (ref "R14") (pin "2") (pinfunction "2_2") (pintype "passive"))
      (node (ref "U3") (pin "6") (pinfunction "CH5_6") (pintype "passive"))
    )
    (net (code "83") (name "Net-(U3-CH6)") (class "Default")
      (node (ref "R10") (pin "1") (pinfunction "1_1") (pintype "passive"))
      (node (ref "R12") (pin "2") (pinfunction "2_2") (pintype "passive"))
      (node (ref "U3") (pin "7") (pinfunction "CH6_7") (pintype "passive"))
    )
    (net (code "84") (name "Net-(U3-CH7)") (class "Default")
      (node (ref "R13") (pin "2") (pinfunction "2_2") (pintype "passive"))
      (node (ref "R8") (pin "1") (pinfunction "1_1") (pintype "passive"))
      (node (ref "U3") (pin "8") (pinfunction "CH7_8") (pintype "passive"))
    )
    (net (code "85") (name "VCC12_IN") (class "Default")
      (node (ref "Q1") (pin "3") (pinfunction "S_3") (pintype "passive"))
      (node (ref "R3") (pin "2") (pinfunction "2_2") (pintype "passive"))
      (node (ref "R4") (pin "2") (pinfunction "2_2") (pintype "passive"))
      (node (ref "T1") (pin "LCP") (pinfunction "P2_LCP") (pintype "passive"))
    )
    (net (code "86") (name "unconnected-(ESP-1-GPIO0-Pad3)") (class "Default")
      (node (ref "ESP-1") (pin "3") (pinfunction "GPIO0_3") (pintype "passive"))
    )
    (net (code "87") (name "unconnected-(ESP-1-GPIO2-Pad2)") (class "Default")
      (node (ref "ESP-1") (pin "2") (pinfunction "GPIO2_2") (pintype "passive"))
    )
    (net (code "88") (name "unconnected-(ESP-1-GPIO16-Pad7)") (class "Default")
      (node (ref "ESP-1") (pin "7") (pinfunction "GPIO16_7") (pintype "passive"))
    )
    (net (code "89") (name "unconnected-(J2-DAT1-Pad8)") (class "Default")
      (node (ref "J2") (pin "8") (pinfunction "DAT1_8") (pintype "passive"))
    )
    (net (code "90") (name "unconnected-(J2-DAT2-Pad1)") (class "Default")
      (node (ref "J2") (pin "1") (pinfunction "DAT2_1") (pintype "passive"))
    )
    (net (code "91") (name "unconnected-(J3-4-Pad5)") (class "Default")
      (node (ref "J3") (pin "5") (pinfunction "4_5") (pintype "passive"))
    )
    (net (code "92") (name "unconnected-(J3-5-Pad4)") (class "Default")
      (node (ref "J3") (pin "4") (pinfunction "5_4") (pintype "passive"))
    )
    (net (code "93") (name "unconnected-(J4-4-Pad5)") (class "Default")
      (node (ref "J4") (pin "5") (pinfunction "4_5") (pintype "passive"))
    )
    (net (code "94") (name "unconnected-(J4-5-Pad4)") (class "Default")
      (node (ref "J4") (pin "4") (pinfunction "5_4") (pintype "passive"))
    )
    (net (code "95") (name "unconnected-(J5-4-Pad5)") (class "Default")
      (node (ref "J5") (pin "5") (pinfunction "4_5") (pintype "passive"))
    )
    (net (code "96") (name "unconnected-(J5-5-Pad4)") (class "Default")
      (node (ref "J5") (pin "4") (pinfunction "5_4") (pintype "passive"))
    )
    (net (code "97") (name "unconnected-(U1-INT-Pad28)") (class "Default")
      (node (ref "U1") (pin "28") (pinfunction "INT_28") (pintype "passive"))
    )
    (net (code "98") (name "unconnected-(U1-NC-Pad1)") (class "Default")
      (node (ref "U1") (pin "1") (pinfunction "NC_1") (pintype "passive"))
    )
    (net (code "99") (name "unconnected-(U1-NC-Pad24)") (class "Default")
      (node (ref "U1") (pin "24") (pinfunction "NC_24") (pintype "passive"))
    )
    (net (code "100") (name "unconnected-(U1-NC-Pad27)") (class "Default")
      (node (ref "U1") (pin "27") (pinfunction "NC_27") (pintype "passive"))
    )
    (net (code "101") (name "unconnected-(U1-WAIT-Pad29)") (class "Default")
      (node (ref "U1") (pin "29") (pinfunction "WAIT_29") (pintype "passive"))
    )
    (net (code "102") (name "unconnected-(X2-Pad6)") (class "Default")
      (node (ref "X2") (pin "6") (pinfunction "6_6") (pintype "power_in"))
    )
  )
)
